# 3_BMS.net
KiCad netlist of a schematic drawn in Altium Designer
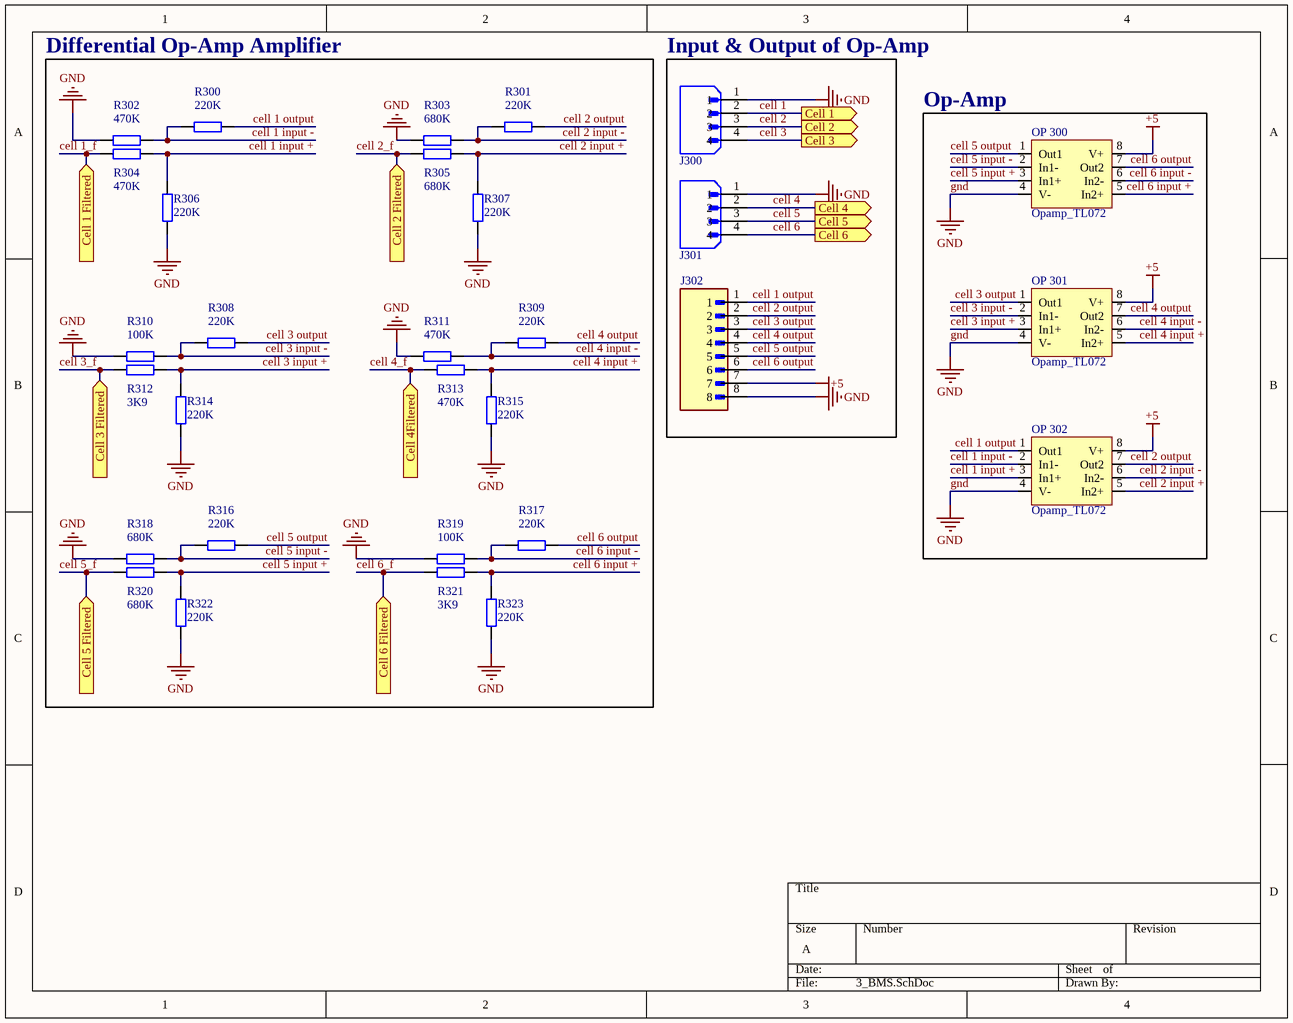
[diagram p0: 3_BMS.SchDoc]

(export (version "E")
  (design (tool "Eeschema 10.0.6"))
  (components
    (comp (ref "J300")
      (value "S4B-XH-A-1")
      (footprint "JST_S4B-XH-A-1")
      (description "Connector Header Through Hole, Right Angle 4 position 0.098 (2.50mm)")
      (fields (field (name "MF") "JST Sales"))
      (libsource (lib "S4B-XH-A-1") (part "S4B-XH-A-1"))
    )
    (comp (ref "J301")
      (value "S4B-XH-A-1")
      (footprint "JST_S4B-XH-A-1")
      (description "Connector Header Through Hole, Right Angle 4 position 0.098 (2.50mm)")
      (fields (field (name "MF") "JST Sales"))
      (libsource (lib "S4B-XH-A-1") (part "S4B-XH-A-1"))
    )
    (comp (ref "J302")
      (value "S8B-XH-A-1")
      (footprint "JST_S8B-XH-A-1")
      (description "Connector Header Through Hole, Right Angle 8 position 0.098 (2.50mm)")
      (fields (field (name "MF") "JST Sales"))
      (libsource (lib "S8B-XH-A-1") (part "S8B-XH-A-1"))
    )
    (comp (ref "OP 300")
      (value "Opamp_TL072")
      (footprint "TL072")
      (libsource (lib "MIA_LIBRARY") (part "Opamp_TL072"))
    )
    (comp (ref "OP 301")
      (value "Opamp_TL072")
      (footprint "TL072")
      (libsource (lib "MIA_LIBRARY") (part "Opamp_TL072"))
    )
    (comp (ref "OP 302")
      (value "Opamp_TL072")
      (footprint "TL072")
      (libsource (lib "MIA_LIBRARY") (part "Opamp_TL072"))
    )
    (comp (ref "R300")
      (value "220K")
      (footprint "RES_0603")
      (description "Resistor SMD 0603")
      (libsource (lib "Schematic-Lib-PhilsLab") (part "RES_0603"))
    )
    (comp (ref "R301")
      (value "220K")
      (footprint "RES_0603")
      (description "Resistor SMD 0603")
      (libsource (lib "Schematic-Lib-PhilsLab") (part "RES_0603"))
    )
    (comp (ref "R302")
      (value "470K")
      (footprint "RES_0805")
      (description "Resistor SMD 0805")
      (libsource (lib "Schematic-Lib-PhilsLab") (part "RES_0805"))
    )
    (comp (ref "R303")
      (value "680K")
      (footprint "RES_0603")
      (description "Resistor SMD 0603")
      (libsource (lib "Schematic-Lib-PhilsLab") (part "RES_0603"))
    )
    (comp (ref "R304")
      (value "470K")
      (footprint "RES_0805")
      (description "Resistor SMD 0805")
      (libsource (lib "Schematic-Lib-PhilsLab") (part "RES_0805"))
    )
    (comp (ref "R305")
      (value "680K")
      (footprint "RES_0603")
      (description "Resistor SMD 0603")
      (libsource (lib "Schematic-Lib-PhilsLab") (part "RES_0603"))
    )
    (comp (ref "R306")
      (value "220K")
      (footprint "RES_0603")
      (description "Resistor SMD 0603")
      (libsource (lib "Schematic-Lib-PhilsLab") (part "RES_0603"))
    )
    (comp (ref "R307")
      (value "220K")
      (footprint "RES_0603")
      (description "Resistor SMD 0603")
      (libsource (lib "Schematic-Lib-PhilsLab") (part "RES_0603"))
    )
    (comp (ref "R308")
      (value "220K")
      (footprint "RES_0603")
      (description "Resistor SMD 0603")
      (libsource (lib "Schematic-Lib-PhilsLab") (part "RES_0603"))
    )
    (comp (ref "R309")
      (value "220K")
      (footprint "RES_0603")
      (description "Resistor SMD 0603")
      (libsource (lib "Schematic-Lib-PhilsLab") (part "RES_0603"))
    )
    (comp (ref "R310")
      (value "100K")
      (footprint "RES_1206")
      (description "Resistor SMD 1206")
      (libsource (lib "Schematic-Lib-PhilsLab") (part "RES_1206"))
    )
    (comp (ref "R311")
      (value "470K")
      (footprint "RES_0805")
      (description "Resistor SMD 0805")
      (libsource (lib "Schematic-Lib-PhilsLab") (part "RES_0805"))
    )
    (comp (ref "R312")
      (value "3K9")
      (footprint "RES_0603")
      (description "Resistor SMD 0603")
      (libsource (lib "Schematic-Lib-PhilsLab") (part "RES_0603"))
    )
    (comp (ref "R313")
      (value "470K")
      (footprint "RES_0805")
      (description "Resistor SMD 0805")
      (libsource (lib "Schematic-Lib-PhilsLab") (part "RES_0805"))
    )
    (comp (ref "R314")
      (value "220K")
      (footprint "RES_0603")
      (description "Resistor SMD 0603")
      (libsource (lib "Schematic-Lib-PhilsLab") (part "RES_0603"))
    )
    (comp (ref "R315")
      (value "220K")
      (footprint "RES_0603")
      (description "Resistor SMD 0603")
      (libsource (lib "Schematic-Lib-PhilsLab") (part "RES_0603"))
    )
    (comp (ref "R316")
      (value "220K")
      (footprint "RES_0603")
      (description "Resistor SMD 0603")
      (libsource (lib "Schematic-Lib-PhilsLab") (part "RES_0603"))
    )
    (comp (ref "R317")
      (value "220K")
      (footprint "RES_0603")
      (description "Resistor SMD 0603")
      (libsource (lib "Schematic-Lib-PhilsLab") (part "RES_0603"))
    )
    (comp (ref "R318")
      (value "680K")
      (footprint "RES_0603")
      (description "Resistor SMD 0603")
      (libsource (lib "Schematic-Lib-PhilsLab") (part "RES_0603"))
    )
    (comp (ref "R319")
      (value "100K")
      (footprint "RES_1206")
      (description "Resistor SMD 1206")
      (libsource (lib "Schematic-Lib-PhilsLab") (part "RES_1206"))
    )
    (comp (ref "R320")
      (value "680K")
      (footprint "RES_0603")
      (description "Resistor SMD 0603")
      (libsource (lib "Schematic-Lib-PhilsLab") (part "RES_0603"))
    )
    (comp (ref "R321")
      (value "3K9")
      (footprint "RES_0603")
      (description "Resistor SMD 0603")
      (libsource (lib "Schematic-Lib-PhilsLab") (part "RES_0603"))
    )
    (comp (ref "R322")
      (value "220K")
      (footprint "RES_0603")
      (description "Resistor SMD 0603")
      (libsource (lib "Schematic-Lib-PhilsLab") (part "RES_0603"))
    )
    (comp (ref "R323")
      (value "220K")
      (footprint "RES_0603")
      (description "Resistor SMD 0603")
      (libsource (lib "Schematic-Lib-PhilsLab") (part "RES_0603"))
    )
  )
  (nets
    (net (code "1") (name "+5") (class "Default")
      (node (ref "J302") (pin "7") (pinfunction "7_7") (pintype "passive"))
      (node (ref "OP 300") (pin "8") (pinfunction "V+_8") (pintype "passive"))
      (node (ref "OP 301") (pin "8") (pinfunction "V+_8") (pintype "passive"))
      (node (ref "OP 302") (pin "8") (pinfunction "V+_8") (pintype "passive"))
    )
    (net (code "2") (name "/cell 1") (class "Default")
      (node (ref "J300") (pin "2") (pinfunction "2_2") (pintype "passive"))
    )
    (net (code "3") (name "/cell 1 input +") (class "Default")
      (node (ref "OP 302") (pin "3") (pinfunction "In1+_3") (pintype "passive"))
      (node (ref "R304") (pin "2") (pinfunction "2_2") (pintype "passive"))
      (node (ref "R306") (pin "2") (pinfunction "2_2") (pintype "passive"))
    )
    (net (code "4") (name "/cell 1 input -") (class "Default")
      (node (ref "OP 302") (pin "2") (pinfunction "In1-_2") (pintype "passive"))
      (node (ref "R300") (pin "1") (pinfunction "1_1") (pintype "passive"))
      (node (ref "R302") (pin "2") (pinfunction "2_2") (pintype "passive"))
    )
    (net (code "5") (name "/cell 1 output") (class "Default")
      (node (ref "J302") (pin "1") (pinfunction "1_1") (pintype "passive"))
      (node (ref "OP 302") (pin "1") (pinfunction "Out1_1") (pintype "passive"))
      (node (ref "R300") (pin "2") (pinfunction "2_2") (pintype "passive"))
    )
    (net (code "6") (name "/cell 1_f") (class "Default")
      (node (ref "R304") (pin "1") (pinfunction "1_1") (pintype "passive"))
    )
    (net (code "7") (name "/cell 2") (class "Default")
      (node (ref "J300") (pin "3") (pinfunction "3_3") (pintype "passive"))
    )
    (net (code "8") (name "/cell 2 input +") (class "Default")
      (node (ref "OP 302") (pin "5") (pinfunction "In2+_5") (pintype "passive"))
      (node (ref "R305") (pin "1") (pinfunction "1_1") (pintype "passive"))
      (node (ref "R307") (pin "2") (pinfunction "2_2") (pintype "passive"))
    )
    (net (code "9") (name "/cell 2 input -") (class "Default")
      (node (ref "OP 302") (pin "6") (pinfunction "In2-_6") (pintype "passive"))
      (node (ref "R301") (pin "1") (pinfunction "1_1") (pintype "passive"))
      (node (ref "R303") (pin "1") (pinfunction "1_1") (pintype "passive"))
    )
    (net (code "10") (name "/cell 2 output") (class "Default")
      (node (ref "J302") (pin "2") (pinfunction "2_2") (pintype "passive"))
      (node (ref "OP 302") (pin "7") (pinfunction "Out2_7") (pintype "passive"))
      (node (ref "R301") (pin "2") (pinfunction "2_2") (pintype "passive"))
    )
    (net (code "11") (name "/cell 2_f") (class "Default")
      (node (ref "R305") (pin "2") (pinfunction "2_2") (pintype "passive"))
    )
    (net (code "12") (name "/cell 3") (class "Default")
      (node (ref "J300") (pin "4") (pinfunction "4_4") (pintype "passive"))
    )
    (net (code "13") (name "/cell 3 input +") (class "Default")
      (node (ref "OP 301") (pin "3") (pinfunction "In1+_3") (pintype "passive"))
      (node (ref "R312") (pin "2") (pinfunction "2_2") (pintype "passive"))
      (node (ref "R314") (pin "2") (pinfunction "2_2") (pintype "passive"))
    )
    (net (code "14") (name "/cell 3 input -") (class "Default")
      (node (ref "OP 301") (pin "2") (pinfunction "In1-_2") (pintype "passive"))
      (node (ref "R308") (pin "1") (pinfunction "1_1") (pintype "passive"))
      (node (ref "R310") (pin "2") (pinfunction "2_2") (pintype "passive"))
    )
    (net (code "15") (name "/cell 3 output") (class "Default")
      (node (ref "J302") (pin "3") (pinfunction "3_3") (pintype "passive"))
      (node (ref "OP 301") (pin "1") (pinfunction "Out1_1") (pintype "passive"))
      (node (ref "R308") (pin "2") (pinfunction "2_2") (pintype "passive"))
    )
    (net (code "16") (name "/cell 3_f") (class "Default")
      (node (ref "R312") (pin "1") (pinfunction "1_1") (pintype "passive"))
    )
    (net (code "17") (name "/cell 4") (class "Default")
      (node (ref "J301") (pin "2") (pinfunction "2_2") (pintype "passive"))
    )
    (net (code "18") (name "/cell 4 input +") (class "Default")
      (node (ref "OP 301") (pin "5") (pinfunction "In2+_5") (pintype "passive"))
      (node (ref "R313") (pin "2") (pinfunction "2_2") (pintype "passive"))
      (node (ref "R315") (pin "2") (pinfunction "2_2") (pintype "passive"))
    )
    (net (code "19") (name "/cell 4 input -") (class "Default")
      (node (ref "OP 301") (pin "6") (pinfunction "In2-_6") (pintype "passive"))
      (node (ref "R309") (pin "1") (pinfunction "1_1") (pintype "passive"))
      (node (ref "R311") (pin "2") (pinfunction "2_2") (pintype "passive"))
    )
    (net (code "20") (name "/cell 4 output") (class "Default")
      (node (ref "J302") (pin "4") (pinfunction "4_4") (pintype "passive"))
      (node (ref "OP 301") (pin "7") (pinfunction "Out2_7") (pintype "passive"))
      (node (ref "R309") (pin "2") (pinfunction "2_2") (pintype "passive"))
    )
    (net (code "21") (name "/cell 4_f") (class "Default")
      (node (ref "R313") (pin "1") (pinfunction "1_1") (pintype "passive"))
    )
    (net (code "22") (name "/cell 5") (class "Default")
      (node (ref "J301") (pin "3") (pinfunction "3_3") (pintype "passive"))
    )
    (net (code "23") (name "/cell 5 input +") (class "Default")
      (node (ref "OP 300") (pin "3") (pinfunction "In1+_3") (pintype "passive"))
      (node (ref "R320") (pin "1") (pinfunction "1_1") (pintype "passive"))
      (node (ref "R322") (pin "2") (pinfunction "2_2") (pintype "passive"))
    )
    (net (code "24") (name "/cell 5 input -") (class "Default")
      (node (ref "OP 300") (pin "2") (pinfunction "In1-_2") (pintype "passive"))
      (node (ref "R316") (pin "1") (pinfunction "1_1") (pintype "passive"))
      (node (ref "R318") (pin "1") (pinfunction "1_1") (pintype "passive"))
    )
    (net (code "25") (name "/cell 5 output") (class "Default")
      (node (ref "J302") (pin "5") (pinfunction "5_5") (pintype "passive"))
      (node (ref "OP 300") (pin "1") (pinfunction "Out1_1") (pintype "passive"))
      (node (ref "R316") (pin "2") (pinfunction "2_2") (pintype "passive"))
    )
    (net (code "26") (name "/cell 5_f") (class "Default")
      (node (ref "R320") (pin "2") (pinfunction "2_2") (pintype "passive"))
    )
    (net (code "27") (name "/cell 6") (class "Default")
      (node (ref "J301") (pin "4") (pinfunction "4_4") (pintype "passive"))
    )
    (net (code "28") (name "/cell 6 input +") (class "Default")
      (node (ref "OP 300") (pin "5") (pinfunction "In2+_5") (pintype "passive"))
      (node (ref "R321") (pin "2") (pinfunction "2_2") (pintype "passive"))
      (node (ref "R323") (pin "2") (pinfunction "2_2") (pintype "passive"))
    )
    (net (code "29") (name "/cell 6 input -") (class "Default")
      (node (ref "OP 300") (pin "6") (pinfunction "In2-_6") (pintype "passive"))
      (node (ref "R317") (pin "1") (pinfunction "1_1") (pintype "passive"))
      (node (ref "R319") (pin "2") (pinfunction "2_2") (pintype "passive"))
    )
    (net (code "30") (name "/cell 6 output") (class "Default")
      (node (ref "J302") (pin "6") (pinfunction "6_6") (pintype "passive"))
      (node (ref "OP 300") (pin "7") (pinfunction "Out2_7") (pintype "passive"))
      (node (ref "R317") (pin "2") (pinfunction "2_2") (pintype "passive"))
    )
    (net (code "31") (name "/cell 6_f") (class "Default")
      (node (ref "R321") (pin "1") (pinfunction "1_1") (pintype "passive"))
    )
    (net (code "32") (name "GND") (class "Default")
      (node (ref "J300") (pin "1") (pinfunction "1_1") (pintype "passive"))
      (node (ref "J301") (pin "1") (pinfunction "1_1") (pintype "passive"))
      (node (ref "J302") (pin "8") (pinfunction "8_8") (pintype "passive"))
      (node (ref "OP 300") (pin "4") (pinfunction "V-_4") (pintype "passive"))
      (node (ref "OP 301") (pin "4") (pinfunction "V-_4") (pintype "passive"))
      (node (ref "OP 302") (pin "4") (pinfunction "V-_4") (pintype "passive"))
      (node (ref "R302") (pin "1") (pinfunction "1_1") (pintype "passive"))
      (node (ref "R303") (pin "2") (pinfunction "2_2") (pintype "passive"))
      (node (ref "R306") (pin "1") (pinfunction "1_1") (pintype "passive"))
      (node (ref "R307") (pin "1") (pinfunction "1_1") (pintype "passive"))
      (node (ref "R310") (pin "1") (pinfunction "1_1") (pintype "passive"))
      (node (ref "R311") (pin "1") (pinfunction "1_1") (pintype "passive"))
      (node (ref "R314") (pin "1") (pinfunction "1_1") (pintype "passive"))
      (node (ref "R315") (pin "1") (pinfunction "1_1") (pintype "passive"))
      (node (ref "R318") (pin "2") (pinfunction "2_2") (pintype "passive"))
      (node (ref "R319") (pin "1") (pinfunction "1_1") (pintype "passive"))
      (node (ref "R322") (pin "1") (pinfunction "1_1") (pintype "passive"))
      (node (ref "R323") (pin "1") (pinfunction "1_1") (pintype "passive"))
    )
  )
)
